# Mechanical.net
KiCad netlist of a schematic drawn in Altium Designer
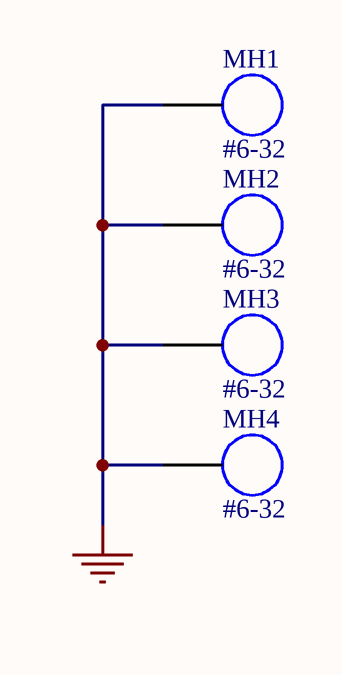
[diagram p0: Mechanical.SchDoc]

(export (version "E")
  (design (tool "Eeschema 10.0.6"))
  (components
    (comp (ref "MH1")
      (value "#6-32")
      (footprint "MH-6-32")
      (description "#6-32 Mounting hole")
      (libsource (lib "CANwheel") (part "#6-32 Mounting Hole"))
    )
    (comp (ref "MH2")
      (value "#6-32")
      (footprint "MH-6-32")
      (description "#6-32 Mounting hole")
      (libsource (lib "CANwheel") (part "#6-32 Mounting Hole"))
    )
    (comp (ref "MH3")
      (value "#6-32")
      (footprint "MH-6-32")
      (description "#6-32 Mounting hole")
      (libsource (lib "CANwheel") (part "#6-32 Mounting Hole"))
    )
    (comp (ref "MH4")
      (value "#6-32")
      (footprint "MH-6-32")
      (description "#6-32 Mounting hole")
      (libsource (lib "CANwheel") (part "#6-32 Mounting Hole"))
    )
  )
  (nets
    (net (code "1") (name "GND") (class "Default")
      (node (ref "MH1") (pin "1") (pinfunction "1_1") (pintype "passive"))
      (node (ref "MH2") (pin "1") (pinfunction "1_1") (pintype "passive"))
      (node (ref "MH3") (pin "1") (pinfunction "1_1") (pintype "passive"))
      (node (ref "MH4") (pin "1") (pinfunction "1_1") (pintype "passive"))
    )
  )
)
